# 2x_relay.net
KiCad netlist of a schematic drawn in EAGLE
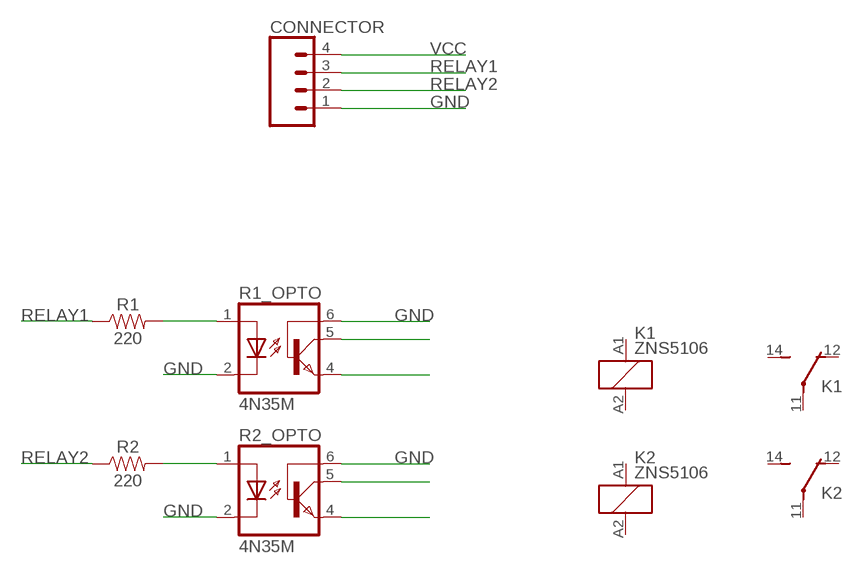
[diagram p0: schematic, sheet 1]

(export (version "E")
  (design (tool "Eeschema 10.0.6"))
  (components
    (comp (ref "CONNECTOR")
      (value "CONN_04POLAR")
      (footprint "eagle-import:MOLEX-1X4")
      (libsource (lib "eagle-import") (part "CONN_04POLAR"))
    )
    (comp (ref "K1")
      (value "ZNS5106")
      (footprint "eagle-import:ZN5")
      (libsource (lib "eagle-import") (part "ZNS5106"))
    )
    (comp (ref "K2")
      (value "ZNS5106")
      (footprint "eagle-import:ZN5")
      (libsource (lib "eagle-import") (part "ZNS5106"))
    )
    (comp (ref "R1")
      (value "220")
      (footprint "eagle-import:AXIAL-0.3")
      (libsource (lib "eagle-import") (part "1KOHM-HORIZ-1/4W-1%"))
    )
    (comp (ref "R1_OPTO")
      (value "4N35M")
      (footprint "eagle-import:DIL06")
      (fields (field (name "MPN") "4N35-M"))
      (libsource (lib "eagle-import") (part "4N?M35"))
    )
    (comp (ref "R2")
      (value "220")
      (footprint "eagle-import:AXIAL-0.3")
      (libsource (lib "eagle-import") (part "1KOHM-HORIZ-1/4W-1%"))
    )
    (comp (ref "R2_OPTO")
      (value "4N35M")
      (footprint "eagle-import:DIL06")
      (fields (field (name "MPN") "4N35-M"))
      (libsource (lib "eagle-import") (part "4N?M35"))
    )
  )
  (nets
    (net (code "1") (name "/GND") (class "Default")
      (node (ref "CONNECTOR") (pin "1") (pinfunction "1_1") (pintype "passive"))
      (node (ref "R1_OPTO") (pin "2") (pinfunction "C_2") (pintype "passive"))
      (node (ref "R1_OPTO") (pin "6") (pinfunction "BAS_6") (pintype "passive"))
      (node (ref "R2_OPTO") (pin "2") (pinfunction "C_2") (pintype "passive"))
      (node (ref "R2_OPTO") (pin "6") (pinfunction "BAS_6") (pintype "passive"))
    )
    (net (code "2") (name "/RELAY1") (class "Default")
      (node (ref "CONNECTOR") (pin "3") (pinfunction "3_3") (pintype "passive"))
      (node (ref "R1") (pin "P$1") (pinfunction "1_P$1") (pintype "passive"))
    )
    (net (code "3") (name "/RELAY2") (class "Default")
      (node (ref "CONNECTOR") (pin "2") (pinfunction "2_2") (pintype "passive"))
      (node (ref "R2") (pin "P$1") (pinfunction "1_P$1") (pintype "passive"))
    )
    (net (code "4") (name "/VCC") (class "Default")
      (node (ref "CONNECTOR") (pin "4") (pinfunction "4_4") (pintype "passive"))
    )
    (net (code "5") (name "Net-(R1-2)") (class "Default")
      (node (ref "R1") (pin "P$2") (pinfunction "2_P$2") (pintype "passive"))
      (node (ref "R1_OPTO") (pin "1") (pinfunction "A_1") (pintype "passive"))
    )
    (net (code "6") (name "Net-(R2-2)") (class "Default")
      (node (ref "R2") (pin "P$2") (pinfunction "2_P$2") (pintype "passive"))
      (node (ref "R2_OPTO") (pin "1") (pinfunction "A_1") (pintype "passive"))
    )
    (net (code "7") (name "unconnected-(K1A-1-PadA1)") (class "Default")
      (node (ref "K1") (pin "A1") (pinfunction "1_A1") (pintype "passive"))
    )
    (net (code "8") (name "unconnected-(K1A-2-PadA2)") (class "Default")
      (node (ref "K1") (pin "A2") (pinfunction "2_A2") (pintype "passive"))
    )
    (net (code "9") (name "unconnected-(K1B-O-Pad12)") (class "Default")
      (node (ref "K1") (pin "12") (pinfunction "O_12") (pintype "passive"))
    )
    (net (code "10") (name "unconnected-(K1B-P-Pad11)") (class "Default")
      (node (ref "K1") (pin "11") (pinfunction "P_11") (pintype "passive"))
    )
    (net (code "11") (name "unconnected-(K1B-S-Pad14)") (class "Default")
      (node (ref "K1") (pin "14") (pinfunction "S_14") (pintype "passive"))
    )
    (net (code "12") (name "unconnected-(K2A-1-PadA1)") (class "Default")
      (node (ref "K2") (pin "A1") (pinfunction "1_A1") (pintype "passive"))
    )
    (net (code "13") (name "unconnected-(K2A-2-PadA2)") (class "Default")
      (node (ref "K2") (pin "A2") (pinfunction "2_A2") (pintype "passive"))
    )
    (net (code "14") (name "unconnected-(K2B-O-Pad12)") (class "Default")
      (node (ref "K2") (pin "12") (pinfunction "O_12") (pintype "passive"))
    )
    (net (code "15") (name "unconnected-(K2B-P-Pad11)") (class "Default")
      (node (ref "K2") (pin "11") (pinfunction "P_11") (pintype "passive"))
    )
    (net (code "16") (name "unconnected-(K2B-S-Pad14)") (class "Default")
      (node (ref "K2") (pin "14") (pinfunction "S_14") (pintype "passive"))
    )
    (net (code "17") (name "unconnected-(R1_OPTO-COL-Pad5)") (class "Default")
      (node (ref "R1_OPTO") (pin "5") (pinfunction "COL_5") (pintype "passive"))
    )
    (net (code "18") (name "unconnected-(R1_OPTO-EMI-Pad4)") (class "Default")
      (node (ref "R1_OPTO") (pin "4") (pinfunction "EMI_4") (pintype "passive"))
    )
    (net (code "19") (name "unconnected-(R2_OPTO-COL-Pad5)") (class "Default")
      (node (ref "R2_OPTO") (pin "5") (pinfunction "COL_5") (pintype "passive"))
    )
    (net (code "20") (name "unconnected-(R2_OPTO-EMI-Pad4)") (class "Default")
      (node (ref "R2_OPTO") (pin "4") (pinfunction "EMI_4") (pintype "passive"))
    )
  )
)
